# XL_N76E003K1__MAIN.net
KiCad netlist of a schematic drawn in Altium Designer
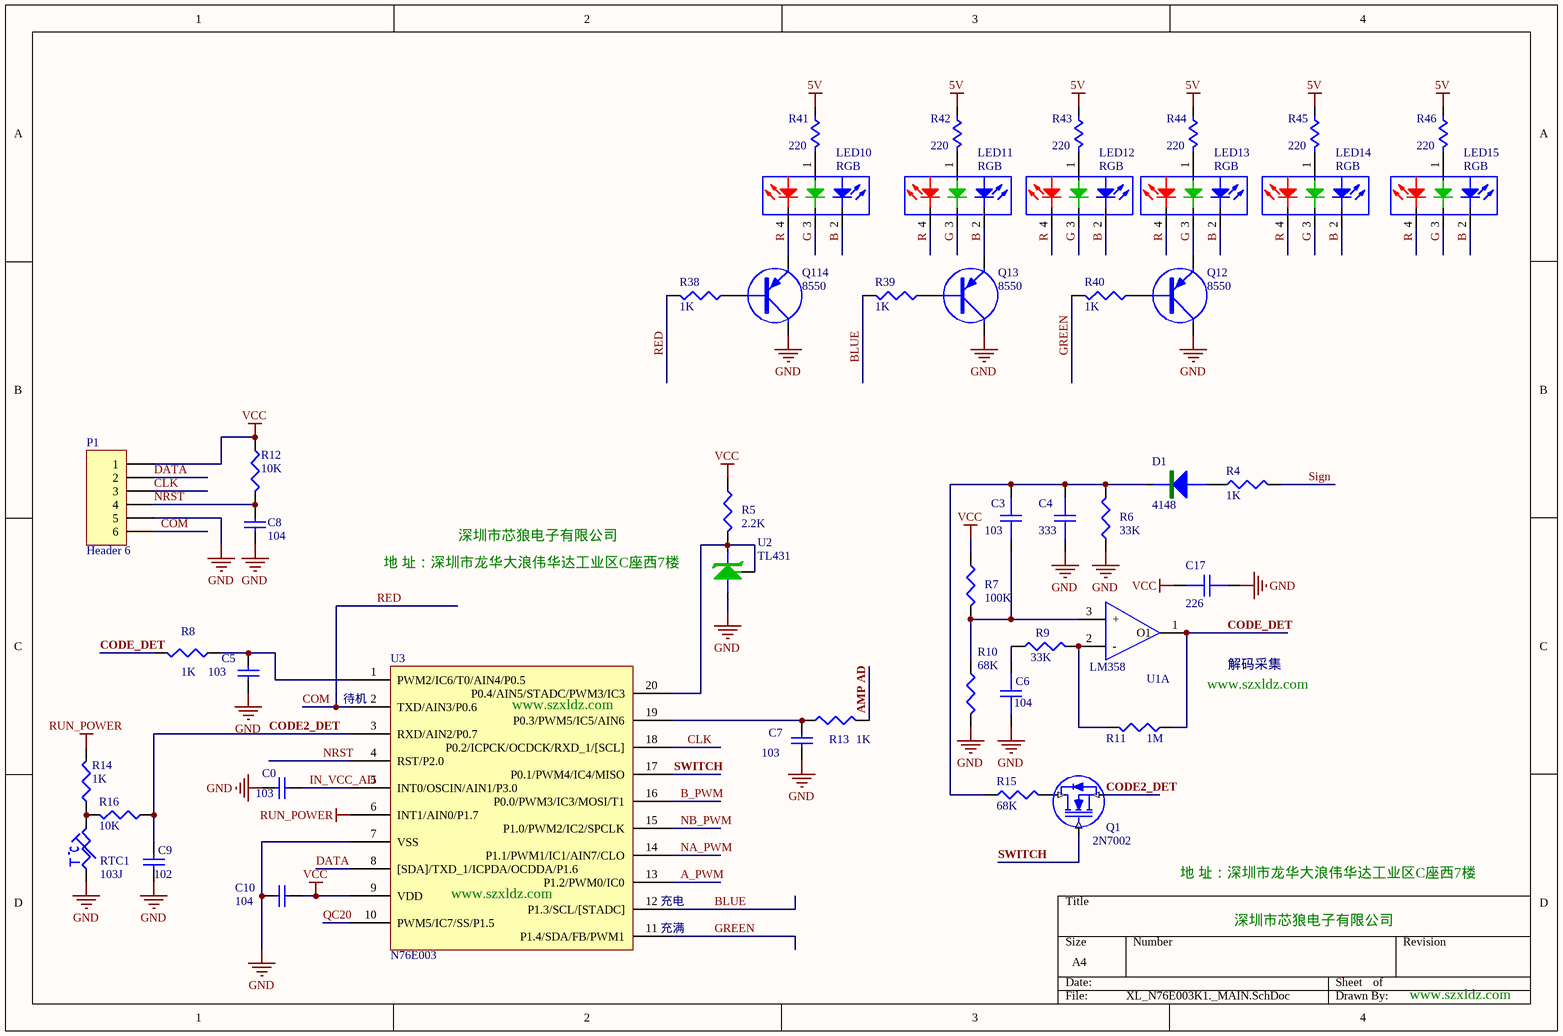
[diagram p0: XL_N76E003K1._MAIN.SchDoc]

(export (version "E")
  (design (tool "Eeschema 10.0.6"))
  (components
    (comp (ref "C0")
      (value "103")
      (footprint "C0402")
      (description "Capacitor")
      (fields (field (name "PUBLISHER") "Altium Limited"))
      (libsource (lib "*") (part "Cap"))
    )
    (comp (ref "C3") (value "103") (footprint "C0402") (libsource (lib "*") (part "CH")))
    (comp (ref "C4") (value "333") (footprint "C0402") (libsource (lib "*") (part "CH")))
    (comp (ref "C5")
      (value "103")
      (footprint "C0402")
      (description "Capacitor")
      (fields (field (name "PUBLISHER") "Altium Limited"))
      (libsource (lib "*") (part "Cap"))
    )
    (comp (ref "C6") (value "104") (footprint "C0402") (libsource (lib "*") (part "CH")))
    (comp (ref "C7")
      (value "103")
      (footprint "C0402")
      (description "Capacitor")
      (fields (field (name "PUBLISHER") "Altium Limited"))
      (libsource (lib "*") (part "Cap"))
    )
    (comp (ref "C8")
      (value "104")
      (footprint "C0402")
      (description "Capacitor")
      (fields (field (name "PUBLISHER") "Altium Limited"))
      (libsource (lib "*") (part "Cap"))
    )
    (comp (ref "C9")
      (value "102")
      (footprint "C0402")
      (description "Capacitor")
      (fields (field (name "PUBLISHER") "Altium Limited"))
      (libsource (lib "*") (part "Cap"))
    )
    (comp (ref "C10")
      (value "104")
      (footprint "C0402")
      (description "Capacitor")
      (fields (field (name "PUBLISHER") "Altium Limited"))
      (libsource (lib "*") (part "Cap"))
    )
    (comp (ref "C17") (value "226") (footprint "C0805") (libsource (lib "*") (part "CH")))
    (comp (ref "D1")
      (value "4148")
      (footprint "sod323")
      (description "1N4001")
      (libsource (lib "*") (part "D0"))
    )
    (comp (ref "LED10") (value "RGB") (footprint "LED-RGB01") (libsource (lib "XiaoQiang") (part "LED05")))
    (comp (ref "LED11") (value "RGB") (footprint "LED-RGB01") (libsource (lib "XiaoQiang") (part "LED05")))
    (comp (ref "LED12") (value "RGB") (footprint "LED-RGB01") (libsource (lib "XiaoQiang") (part "LED05")))
    (comp (ref "LED13") (value "RGB") (footprint "LED-RGB01") (libsource (lib "XiaoQiang") (part "LED05")))
    (comp (ref "LED14") (value "RGB") (footprint "LED-RGB01") (libsource (lib "XiaoQiang") (part "LED05")))
    (comp (ref "LED15") (value "RGB") (footprint "LED-RGB01") (libsource (lib "XiaoQiang") (part "LED05")))
    (comp (ref "P1")
      (value "Header 6")
      (footprint "SPIN6")
      (description "Header, 6-Pin")
      (fields (field (name "PUBLISHER") "Altium Limited"))
      (libsource (lib "Miscellaneous Connectors") (part "Header 6"))
    )
    (comp (ref "Q1") (value "2N7002") (footprint "SOT-23B") (libsource (lib "lxzschlib") (part "MOSFETN")))
    (comp (ref "Q12") (value "8550") (footprint "SOT-23") (libsource (lib "lxzschlib") (part "PNP")))
    (comp (ref "Q13") (value "8550") (footprint "SOT-23") (libsource (lib "lxzschlib") (part "PNP")))
    (comp (ref "Q114") (value "8550") (footprint "SOT-23") (libsource (lib "lxzschlib") (part "PNP")))
    (comp (ref "R4") (value "1K") (footprint "R0402") (libsource (lib "*") (part "R")))
    (comp (ref "R5") (value "2.2K") (footprint "R0402") (description "1K") (libsource (lib "*") (part "R")))
    (comp (ref "R6") (value "33K") (footprint "R0402") (description "1K") (libsource (lib "*") (part "R")))
    (comp (ref "R7") (value "100K") (footprint "R0402") (description "1K") (libsource (lib "*") (part "R")))
    (comp (ref "R8") (value "1K") (footprint "R0402") (libsource (lib "*") (part "R")))
    (comp (ref "R9") (value "33K") (footprint "R0402") (description "1K") (libsource (lib "*") (part "R")))
    (comp (ref "R10") (value "68K") (footprint "R0402") (description "1K") (libsource (lib "*") (part "R")))
    (comp (ref "R11") (value "1M") (footprint "R0402") (description "1K") (libsource (lib "*") (part "R")))
    (comp (ref "R12") (value "10K") (footprint "R0402") (libsource (lib "*") (part "R")))
    (comp (ref "R13") (value "1K") (footprint "R0402") (libsource (lib "*") (part "R")))
    (comp (ref "R14") (value "1K") (footprint "R0402") (libsource (lib "lxzschlib") (part "R")))
    (comp (ref "R15") (value "68K") (footprint "R0402") (description "1K") (libsource (lib "*") (part "R")))
    (comp (ref "R16")
      (value "10K")
      (footprint "R0402")
      (description "1K")
      (libsource (lib "lxzschlib") (part "R"))
    )
    (comp (ref "R38") (value "1K") (libsource (lib "lxzschlib") (part "R")))
    (comp (ref "R39") (value "1K") (libsource (lib "lxzschlib") (part "R")))
    (comp (ref "R40") (value "1K") (libsource (lib "lxzschlib") (part "R")))
    (comp (ref "R41") (value "220") (footprint "R0603") (libsource (lib "XiaoQiang") (part "Res01")))
    (comp (ref "R42") (value "220") (footprint "R0603") (libsource (lib "XiaoQiang") (part "Res01")))
    (comp (ref "R43") (value "220") (footprint "R0603") (libsource (lib "XiaoQiang") (part "Res01")))
    (comp (ref "R44") (value "220") (footprint "R0603") (libsource (lib "XiaoQiang") (part "Res01")))
    (comp (ref "R45") (value "220") (footprint "R0603") (libsource (lib "XiaoQiang") (part "Res01")))
    (comp (ref "R46") (value "220") (footprint "R0603") (libsource (lib "XiaoQiang") (part "Res01")))
    (comp (ref "RTC1") (value "103J") (footprint "R0402") (libsource (lib "lxzschlib") (part "RTC")))
    (comp (ref "U1") (value "LM358") (footprint "SOP8") (libsource (lib "lxzschlib") (part "4558")))
    (comp (ref "U2")
      (value "TL431")
      (footprint "SOT-23-431")
      (description "IC")
      (libsource (lib "lxzschlib") (part "IC TL431"))
    )
    (comp (ref "U3") (value "N76E003") (footprint "SOP20") (libsource (lib "BEE802_V11") (part "103F")))
  )
  (nets
    (net (code "1") (name "/AMP AD") (class "Default") (node (ref "R13") (pin "2") (pintype "passive")))
    (net (code "2") (name "/A_PWM") (class "Default")
      (node (ref "U3") (pin "13") (pinfunction "P1.2/PWM0/IC0_13") (pintype "passive"))
    )
    (net (code "3") (name "/B") (class "Default")
      (node (ref "LED10") (pin "2") (pinfunction "A_2") (pintype "passive"))
      (node (ref "LED11") (pin "2") (pinfunction "A_2") (pintype "passive"))
      (node (ref "LED12") (pin "2") (pinfunction "A_2") (pintype "passive"))
      (node (ref "LED13") (pin "2") (pinfunction "A_2") (pintype "passive"))
      (node (ref "LED14") (pin "2") (pinfunction "A_2") (pintype "passive"))
      (node (ref "LED15") (pin "2") (pinfunction "A_2") (pintype "passive"))
      (node (ref "Q13") (pin "E") (pintype "passive"))
    )
    (net (code "4") (name "/BLUE") (class "Default")
      (node (ref "R39") (pin "2") (pintype "passive"))
      (node (ref "U3") (pin "12") (pinfunction "P1.3/SCL/[STADC]_12") (pintype "passive"))
    )
    (net (code "5") (name "/B_PWM") (class "Default")
      (node (ref "U3") (pin "16") (pinfunction "P0.0/PWM3/IC3/MOSI/T1_16") (pintype "passive"))
    )
    (net (code "6") (name "/CLK") (class "Default")
      (node (ref "P1") (pin "3") (pinfunction "3_3") (pintype "passive"))
      (node (ref "U3") (pin "18") (pinfunction "P0.2/ICPCK/OCDCK/RXD_1/[SCL]_18") (pintype "passive"))
    )
    (net (code "7") (name "/CODE2_DET") (class "Default")
      (node (ref "C9") (pin "2") (pinfunction "2_2") (pintype "passive"))
      (node (ref "Q1") (pin "E") (pinfunction "S_E") (pintype "input"))
      (node (ref "R16") (pin "1") (pintype "passive"))
      (node (ref "U3") (pin "3") (pinfunction "RXD/AIN2/P0.7_3") (pintype "passive"))
    )
    (net (code "8") (name "/CODE_DET") (class "Default")
      (node (ref "R11") (pin "1") (pintype "passive"))
      (node (ref "R8") (pin "2") (pintype "passive"))
      (node (ref "U1") (pin "1") (pinfunction "O1_1") (pintype "passive"))
    )
    (net (code "9") (name "/COM") (class "Default")
      (node (ref "P1") (pin "6") (pinfunction "6_6") (pintype "passive"))
      (node (ref "R38") (pin "2") (pintype "passive"))
      (node (ref "U3") (pin "2") (pinfunction "TXD/AIN3/P0.6_2") (pintype "passive"))
    )
    (net (code "10") (name "/DATA") (class "Default")
      (node (ref "P1") (pin "2") (pinfunction "2_2") (pintype "passive"))
      (node (ref "U3") (pin "8") (pinfunction "[SDA]/TXD_1/ICPDA/OCDDA/P1.6_8") (pintype "passive"))
    )
    (net (code "11") (name "/G") (class "Default")
      (node (ref "LED10") (pin "3") (pinfunction "2_3") (pintype "passive"))
      (node (ref "LED11") (pin "3") (pinfunction "2_3") (pintype "passive"))
      (node (ref "LED12") (pin "3") (pinfunction "2_3") (pintype "passive"))
      (node (ref "LED13") (pin "3") (pinfunction "2_3") (pintype "passive"))
      (node (ref "LED14") (pin "3") (pinfunction "2_3") (pintype "passive"))
      (node (ref "LED15") (pin "3") (pinfunction "2_3") (pintype "passive"))
      (node (ref "Q12") (pin "E") (pintype "passive"))
    )
    (net (code "12") (name "/GREEN") (class "Default")
      (node (ref "R40") (pin "2") (pintype "passive"))
      (node (ref "U3") (pin "11") (pinfunction "P1.4/SDA/FB/PWM1_11") (pintype "passive"))
    )
    (net (code "13") (name "/IN_VCC_AD") (class "Default")
      (node (ref "C0") (pin "2") (pinfunction "2_2") (pintype "passive"))
      (node (ref "U3") (pin "5") (pinfunction "INT0/OSCIN/AIN1/P3.0_5") (pintype "passive"))
    )
    (net (code "14") (name "/NA_PWM") (class "Default")
      (node (ref "U3") (pin "14") (pinfunction "P1.1/PWM1/IC1/AIN7/CLO_14") (pintype "passive"))
    )
    (net (code "15") (name "/NB_PWM") (class "Default")
      (node (ref "U3") (pin "15") (pinfunction "P1.0/PWM2/IC2/SPCLK_15") (pintype "passive"))
    )
    (net (code "16") (name "/NRST") (class "Default")
      (node (ref "C8") (pin "1") (pinfunction "1_1") (pintype "passive"))
      (node (ref "P1") (pin "4") (pinfunction "4_4") (pintype "passive"))
      (node (ref "R12") (pin "2") (pintype "passive"))
      (node (ref "U3") (pin "4") (pinfunction "RST/P2.0_4") (pintype "passive"))
    )
    (net (code "17") (name "/QC20") (class "Default")
      (node (ref "U3") (pin "10") (pinfunction "PWM5/IC7/SS/P1.5_10") (pintype "passive"))
    )
    (net (code "18") (name "/R") (class "Default")
      (node (ref "LED10") (pin "4") (pinfunction "2_4") (pintype "passive"))
      (node (ref "LED11") (pin "4") (pinfunction "2_4") (pintype "passive"))
      (node (ref "LED12") (pin "4") (pinfunction "2_4") (pintype "passive"))
      (node (ref "LED13") (pin "4") (pinfunction "2_4") (pintype "passive"))
      (node (ref "LED14") (pin "4") (pinfunction "2_4") (pintype "passive"))
      (node (ref "LED15") (pin "4") (pinfunction "2_4") (pintype "passive"))
      (node (ref "Q114") (pin "E") (pintype "passive"))
    )
    (net (code "19") (name "/SWITCH") (class "Default")
      (node (ref "Q1") (pin "B") (pinfunction "G_B") (pintype "input"))
      (node (ref "U3") (pin "17") (pinfunction "P0.1/PWM4/IC4/MISO_17") (pintype "passive"))
    )
    (net (code "20") (name "/Sign") (class "Default") (node (ref "R4") (pin "2") (pintype "passive")))
    (net (code "21") (name "5V") (class "Default")
      (node (ref "R41") (pin "1") (pinfunction "1_1") (pintype "passive"))
      (node (ref "R42") (pin "1") (pinfunction "1_1") (pintype "passive"))
      (node (ref "R43") (pin "1") (pinfunction "1_1") (pintype "passive"))
      (node (ref "R44") (pin "1") (pinfunction "1_1") (pintype "passive"))
      (node (ref "R45") (pin "1") (pinfunction "1_1") (pintype "passive"))
      (node (ref "R46") (pin "1") (pinfunction "1_1") (pintype "passive"))
    )
    (net (code "22") (name "GND") (class "Default")
      (node (ref "C0") (pin "1") (pinfunction "1_1") (pintype "passive"))
      (node (ref "C10") (pin "1") (pinfunction "1_1") (pintype "passive"))
      (node (ref "C17") (pin "1") (pintype "passive"))
      (node (ref "C4") (pin "1") (pintype "passive"))
      (node (ref "C5") (pin "1") (pinfunction "1_1") (pintype "passive"))
      (node (ref "C6") (pin "1") (pintype "passive"))
      (node (ref "C7") (pin "2") (pinfunction "2_2") (pintype "passive"))
      (node (ref "C8") (pin "2") (pinfunction "2_2") (pintype "passive"))
      (node (ref "C9") (pin "1") (pinfunction "1_1") (pintype "passive"))
      (node (ref "P1") (pin "5") (pinfunction "5_5") (pintype "passive"))
      (node (ref "Q114") (pin "C") (pintype "passive"))
      (node (ref "Q12") (pin "C") (pintype "passive"))
      (node (ref "Q13") (pin "C") (pintype "passive"))
      (node (ref "R10") (pin "2") (pintype "passive"))
      (node (ref "R6") (pin "1") (pintype "passive"))
      (node (ref "RTC1") (pin "1") (pintype "passive"))
      (node (ref "U2") (pin "1") (pintype "passive"))
      (node (ref "U3") (pin "7") (pinfunction "VSS_7") (pintype "passive"))
    )
    (net (code "23") (name "Net-(C3-Pad1)") (class "Default")
      (node (ref "C3") (pin "1") (pintype "passive"))
      (node (ref "C4") (pin "2") (pintype "passive"))
      (node (ref "D1") (pin "2") (pintype "passive"))
      (node (ref "R15") (pin "1") (pintype "passive"))
      (node (ref "R6") (pin "2") (pintype "passive"))
    )
    (net (code "24") (name "Net-(C6-Pad2)") (class "Default")
      (node (ref "C6") (pin "2") (pintype "passive"))
      (node (ref "R9") (pin "1") (pintype "passive"))
    )
    (net (code "25") (name "Net-(D1-Pad1)") (class "Default")
      (node (ref "D1") (pin "1") (pintype "passive"))
      (node (ref "R4") (pin "1") (pintype "passive"))
    )
    (net (code "26") (name "Net-(LED10-A-Pad1)") (class "Default")
      (node (ref "LED10") (pin "1") (pinfunction "A_1") (pintype "passive"))
      (node (ref "R41") (pin "2") (pinfunction "2_2") (pintype "passive"))
    )
    (net (code "27") (name "Net-(LED11-A-Pad1)") (class "Default")
      (node (ref "LED11") (pin "1") (pinfunction "A_1") (pintype "passive"))
      (node (ref "R42") (pin "2") (pinfunction "2_2") (pintype "passive"))
    )
    (net (code "28") (name "Net-(LED12-A-Pad1)") (class "Default")
      (node (ref "LED12") (pin "1") (pinfunction "A_1") (pintype "passive"))
      (node (ref "R43") (pin "2") (pinfunction "2_2") (pintype "passive"))
    )
    (net (code "29") (name "Net-(LED13-A-Pad1)") (class "Default")
      (node (ref "LED13") (pin "1") (pinfunction "A_1") (pintype "passive"))
      (node (ref "R44") (pin "2") (pinfunction "2_2") (pintype "passive"))
    )
    (net (code "30") (name "Net-(LED14-A-Pad1)") (class "Default")
      (node (ref "LED14") (pin "1") (pinfunction "A_1") (pintype "passive"))
      (node (ref "R45") (pin "2") (pinfunction "2_2") (pintype "passive"))
    )
    (net (code "31") (name "Net-(LED15-A-Pad1)") (class "Default")
      (node (ref "LED15") (pin "1") (pinfunction "A_1") (pintype "passive"))
      (node (ref "R46") (pin "2") (pinfunction "2_2") (pintype "passive"))
    )
    (net (code "32") (name "Net-(Q1-D)") (class "Default")
      (node (ref "Q1") (pin "C") (pinfunction "D_C") (pintype "input"))
      (node (ref "R15") (pin "2") (pintype "passive"))
    )
    (net (code "33") (name "Net-(Q12-PadB)") (class "Default")
      (node (ref "Q12") (pin "B") (pintype "passive"))
      (node (ref "R40") (pin "1") (pintype "passive"))
    )
    (net (code "34") (name "Net-(Q13-PadB)") (class "Default")
      (node (ref "Q13") (pin "B") (pintype "passive"))
      (node (ref "R39") (pin "1") (pintype "passive"))
    )
    (net (code "35") (name "Net-(Q114-PadB)") (class "Default")
      (node (ref "Q114") (pin "B") (pintype "passive"))
      (node (ref "R38") (pin "1") (pintype "passive"))
    )
    (net (code "36") (name "Net-(R14-Pad1)") (class "Default")
      (node (ref "R14") (pin "1") (pintype "passive"))
      (node (ref "R16") (pin "2") (pintype "passive"))
      (node (ref "RTC1") (pin "2") (pintype "passive"))
    )
    (net (code "37") (name "Net-(U1A-+)") (class "Default")
      (node (ref "C3") (pin "2") (pintype "passive"))
      (node (ref "R10") (pin "1") (pintype "passive"))
      (node (ref "R7") (pin "2") (pintype "passive"))
      (node (ref "U1") (pin "3") (pinfunction "+_3") (pintype "passive"))
    )
    (net (code "38") (name "Net-(U1A--)") (class "Default")
      (node (ref "R11") (pin "2") (pintype "passive"))
      (node (ref "R9") (pin "2") (pintype "passive"))
      (node (ref "U1") (pin "2") (pinfunction "-_2") (pintype "passive"))
    )
    (net (code "39") (name "Net-(U3-P0.3{slash}PWM5{slash}IC5{slash}AIN6)") (class "Default")
      (node (ref "C7") (pin "1") (pinfunction "1_1") (pintype "passive"))
      (node (ref "R13") (pin "1") (pintype "passive"))
      (node (ref "U3") (pin "19") (pinfunction "P0.3/PWM5/IC5/AIN6_19") (pintype "passive"))
    )
    (net (code "40") (name "Net-(U3-P0.4{slash}AIN5{slash}STADC{slash}PWM3{slash}IC3)") (class "Default")
      (node (ref "R5") (pin "2") (pintype "passive"))
      (node (ref "U2") (pin "2") (pintype "passive"))
      (node (ref "U2") (pin "3") (pintype "passive"))
      (node (ref "U3") (pin "20") (pinfunction "P0.4/AIN5/STADC/PWM3/IC3_20") (pintype "passive"))
    )
    (net (code "41") (name "Net-(U3-PWM2{slash}IC6{slash}T0{slash}AIN4{slash}P0.5)") (class "Default")
      (node (ref "C5") (pin "2") (pinfunction "2_2") (pintype "passive"))
      (node (ref "R8") (pin "1") (pintype "passive"))
      (node (ref "U3") (pin "1") (pinfunction "PWM2/IC6/T0/AIN4/P0.5_1") (pintype "passive"))
    )
    (net (code "42") (name "RUN_POWER") (class "Default")
      (node (ref "R14") (pin "2") (pintype "passive"))
      (node (ref "U3") (pin "6") (pinfunction "INT1/AIN0/P1.7_6") (pintype "passive"))
    )
    (net (code "43") (name "VCC") (class "Default")
      (node (ref "C10") (pin "2") (pinfunction "2_2") (pintype "passive"))
      (node (ref "C17") (pin "2") (pintype "passive"))
      (node (ref "P1") (pin "1") (pinfunction "1_1") (pintype "passive"))
      (node (ref "R12") (pin "1") (pintype "passive"))
      (node (ref "R5") (pin "1") (pintype "passive"))
      (node (ref "R7") (pin "1") (pintype "passive"))
      (node (ref "U3") (pin "9") (pinfunction "VDD_9") (pintype "passive"))
    )
  )
)
